# ANA_FE.net
KiCad netlist of a schematic drawn in Altium Designer
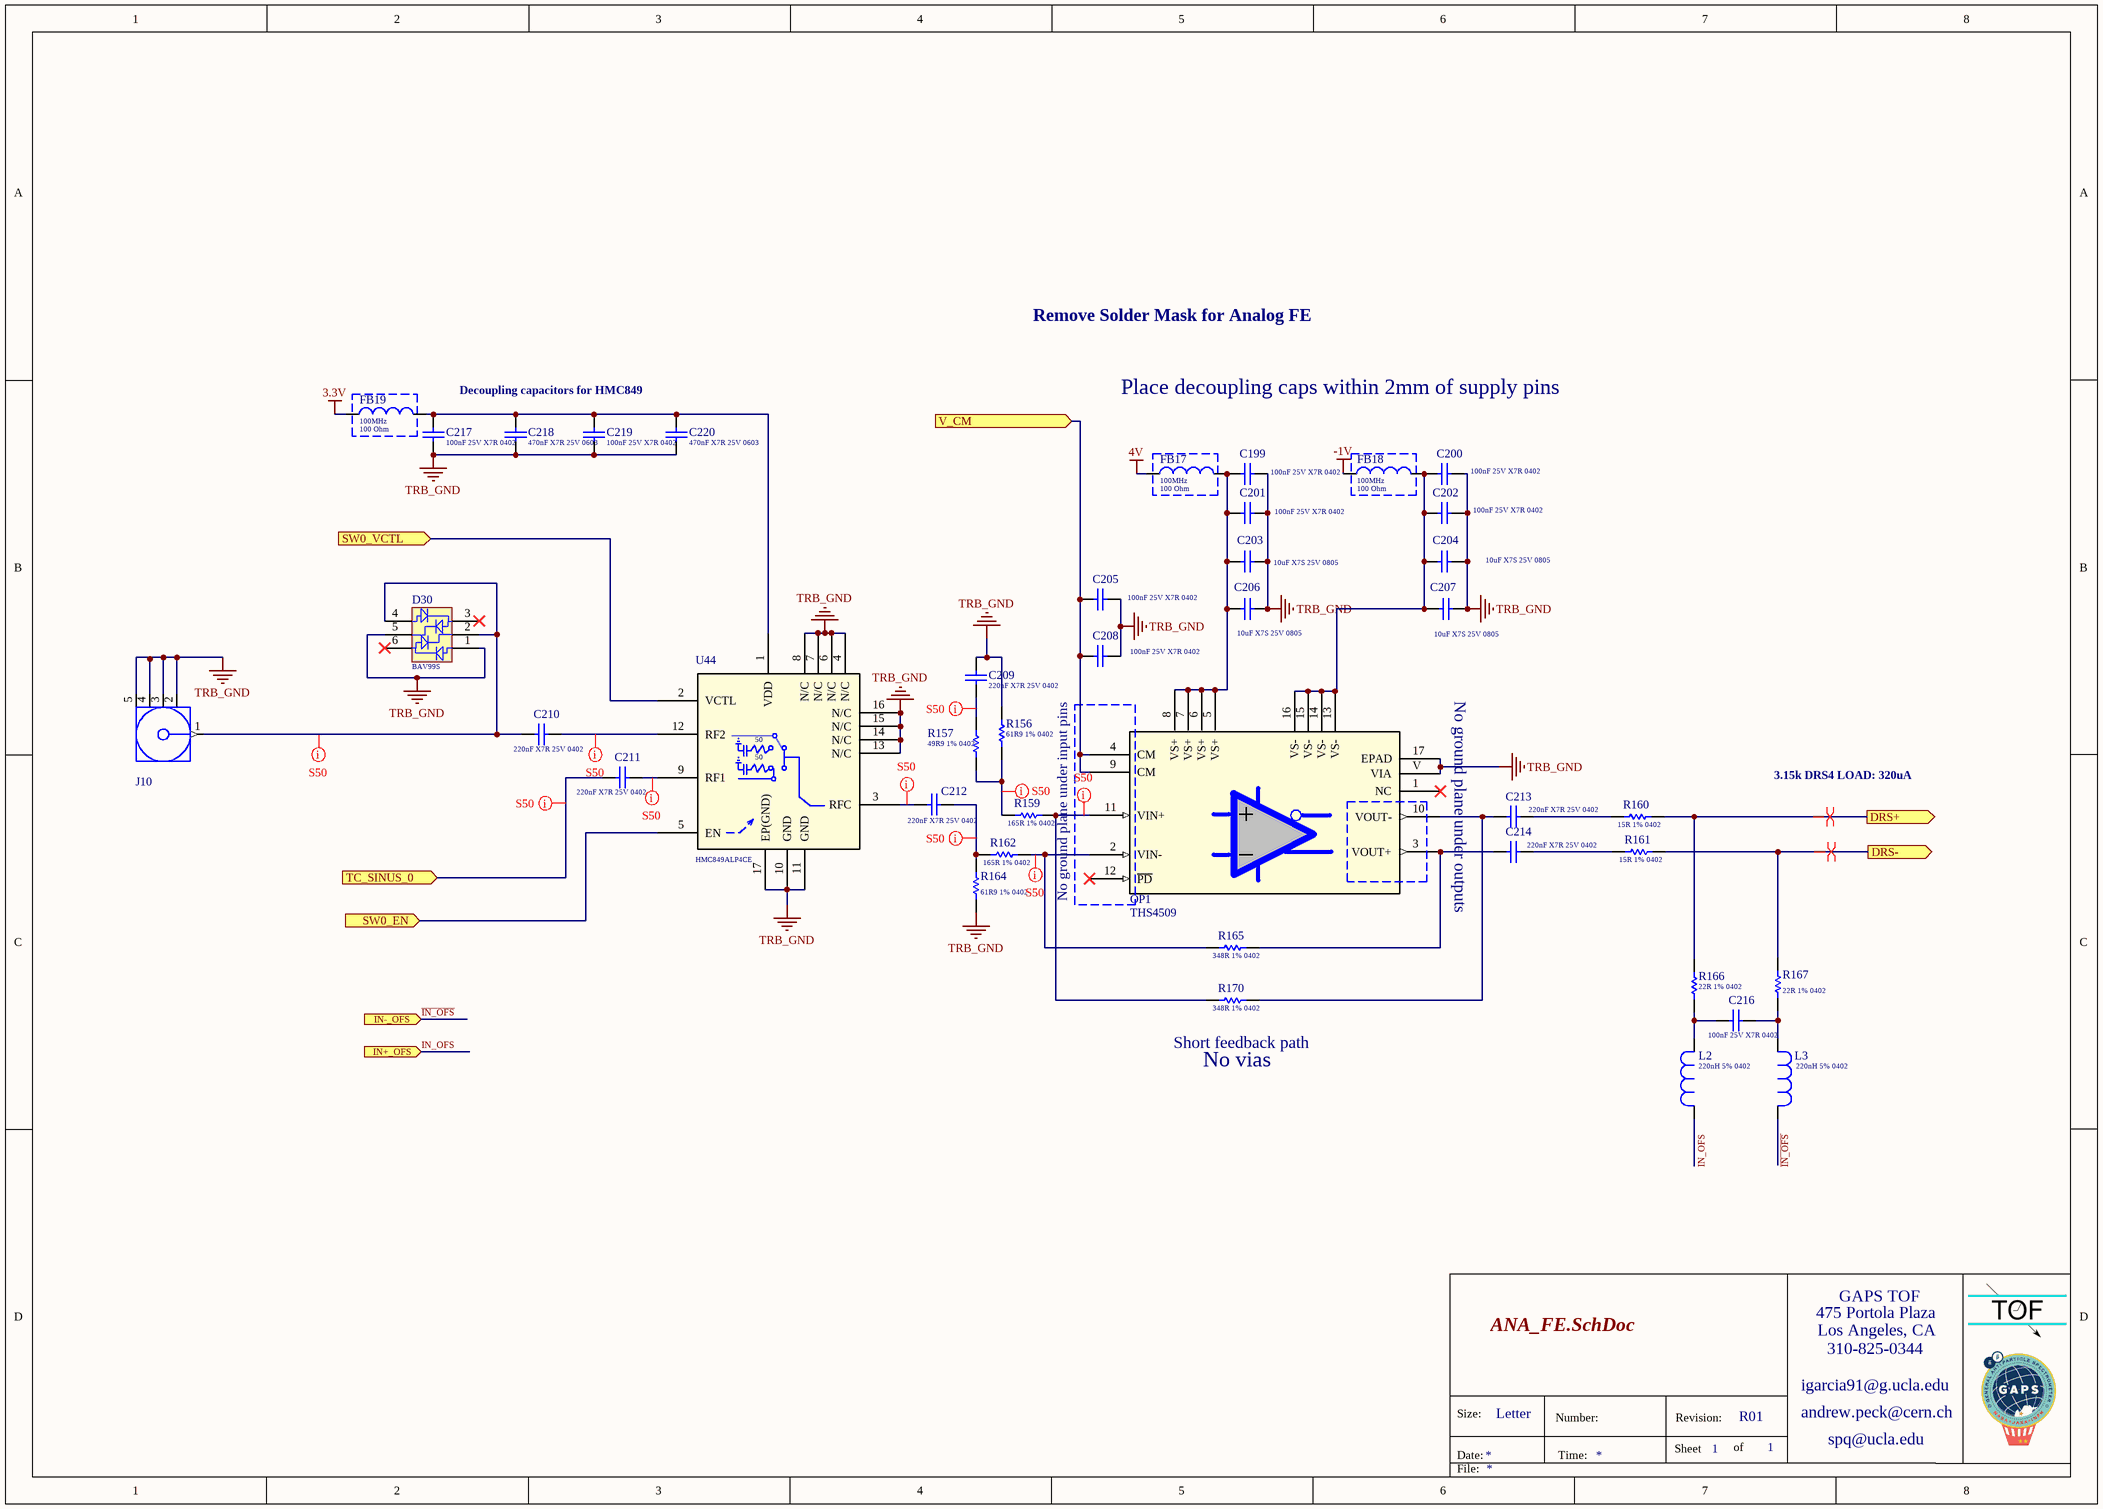
[diagram p0: ANA_FE.SchDoc]

(export (version "E")
  (design (tool "Eeschema 10.0.6"))
  (components
    (comp (ref "C199")
      (value "Cap_Taiyo_Yuden_TMK105B7104KV-FR_100nF")
      (footprint "Cap_Taiyo_Yuden_TMK105B7104KV-FR_100nF")
      (description "CAP CER 100nF 25V X7R 0402")
      (fields (field (name "CAPACITANCE") "100nF 25V X7R 0402"))
      (libsource (lib "Cap_Taiyo_Yuden_TMK105B7104KV-FR_100nF") (part "Cap_Taiyo_Yuden_TMK105B7104KV-FR_100nF"))
    )
    (comp (ref "C200")
      (value "Cap_Taiyo_Yuden_TMK105B7104KV-FR_100nF")
      (footprint "Cap_Taiyo_Yuden_TMK105B7104KV-FR_100nF")
      (description "CAP CER 100nF 25V X7R 0402")
      (fields (field (name "CAPACITANCE") "100nF 25V X7R 0402"))
      (libsource (lib "Cap_Taiyo_Yuden_TMK105B7104KV-FR_100nF") (part "Cap_Taiyo_Yuden_TMK105B7104KV-FR_100nF"))
    )
    (comp (ref "C201")
      (value "Cap_Taiyo_Yuden_TMK105B7104KV-FR_100nF")
      (footprint "Cap_Taiyo_Yuden_TMK105B7104KV-FR_100nF")
      (description "CAP CER 100nF 25V X7R 0402")
      (fields (field (name "CAPACITANCE") "100nF 25V X7R 0402"))
      (libsource (lib "Cap_Taiyo_Yuden_TMK105B7104KV-FR_100nF") (part "Cap_Taiyo_Yuden_TMK105B7104KV-FR_100nF"))
    )
    (comp (ref "C202")
      (value "Cap_Taiyo_Yuden_TMK105B7104KV-FR_100nF")
      (footprint "Cap_Taiyo_Yuden_TMK105B7104KV-FR_100nF")
      (description "CAP CER 100nF 25V X7R 0402")
      (fields (field (name "CAPACITANCE") "100nF 25V X7R 0402"))
      (libsource (lib "Cap_Taiyo_Yuden_TMK105B7104KV-FR_100nF") (part "Cap_Taiyo_Yuden_TMK105B7104KV-FR_100nF"))
    )
    (comp (ref "C203")
      (value "Cap_Murata_ GRM21BC71E106ME11L_10uF")
      (footprint "Cap_Murata_ GRM21BC71E106ME11L_10uF")
      (description "CAP CER 10uF 25V X7R 0805")
      (fields (field (name "CAPACITANCE") "10uF X7S 25V 0805"))
      (libsource (lib "Cap_Murata_ GRM21BC71E106ME11L_10uF") (part "Cap_Murata_ GRM21BC71E106ME11L_10uF"))
    )
    (comp (ref "C204")
      (value "Cap_Murata_ GRM21BC71E106ME11L_10uF")
      (footprint "Cap_Murata_ GRM21BC71E106ME11L_10uF")
      (description "CAP CER 10uF 25V X7R 0805")
      (fields (field (name "CAPACITANCE") "10uF X7S 25V 0805"))
      (libsource (lib "Cap_Murata_ GRM21BC71E106ME11L_10uF") (part "Cap_Murata_ GRM21BC71E106ME11L_10uF"))
    )
    (comp (ref "C205")
      (value "Cap_Taiyo_Yuden_TMK105B7104KV-FR_100nF")
      (footprint "Cap_Taiyo_Yuden_TMK105B7104KV-FR_100nF")
      (description "CAP CER 100nF 25V X7R 0402")
      (fields (field (name "CAPACITANCE") "100nF 25V X7R 0402"))
      (libsource (lib "Cap_Taiyo_Yuden_TMK105B7104KV-FR_100nF") (part "Cap_Taiyo_Yuden_TMK105B7104KV-FR_100nF"))
    )
    (comp (ref "C206")
      (value "Cap_Murata_ GRM21BC71E106ME11L_10uF")
      (footprint "Cap_Murata_ GRM21BC71E106ME11L_10uF")
      (description "CAP CER 10uF 25V X7R 0805")
      (fields (field (name "CAPACITANCE") "10uF X7S 25V 0805"))
      (libsource (lib "Cap_Murata_ GRM21BC71E106ME11L_10uF") (part "Cap_Murata_ GRM21BC71E106ME11L_10uF"))
    )
    (comp (ref "C207")
      (value "Cap_Murata_ GRM21BC71E106ME11L_10uF")
      (footprint "Cap_Murata_ GRM21BC71E106ME11L_10uF")
      (description "CAP CER 10uF 25V X7R 0805")
      (fields (field (name "CAPACITANCE") "10uF X7S 25V 0805"))
      (libsource (lib "Cap_Murata_ GRM21BC71E106ME11L_10uF") (part "Cap_Murata_ GRM21BC71E106ME11L_10uF"))
    )
    (comp (ref "C208")
      (value "Cap_Taiyo_Yuden_TMK105B7104KV-FR_100nF")
      (footprint "Cap_Taiyo_Yuden_TMK105B7104KV-FR_100nF")
      (description "CAP CER 100nF 25V X7R 0402")
      (fields (field (name "CAPACITANCE") "100nF 25V X7R 0402"))
      (libsource (lib "Cap_Taiyo_Yuden_TMK105B7104KV-FR_100nF") (part "Cap_Taiyo_Yuden_TMK105B7104KV-FR_100nF"))
    )
    (comp (ref "C209")
      (value "Cap_TDK_C1608X5R1A106M080AC_220nF")
      (footprint "Cap_TDK_C1608X5R1A106M080AC_220nF")
      (description "CAP CER 220nF 50V X7R 0402")
      (fields (field (name "CAPACITANCE") "220nF X7R 25V 0402"))
      (libsource (lib "Cap_TDK_C1608X5R1A106M080AC_220nF") (part "Cap_TDK_C1608X5R1A106M080AC_220nF"))
    )
    (comp (ref "C210")
      (value "Cap_TDK_C1608X5R1A106M080AC_220nF")
      (footprint "Cap_TDK_C1608X5R1A106M080AC_220nF")
      (description "CAP CER 220nF 50V X7R 0402")
      (fields (field (name "CAPACITANCE") "220nF X7R 25V 0402"))
      (libsource (lib "Cap_TDK_C1608X5R1A106M080AC_220nF") (part "Cap_TDK_C1608X5R1A106M080AC_220nF"))
    )
    (comp (ref "C211")
      (value "Cap_TDK_C1608X5R1A106M080AC_220nF")
      (footprint "Cap_TDK_C1608X5R1A106M080AC_220nF")
      (description "CAP CER 220nF 50V X7R 0402")
      (fields (field (name "CAPACITANCE") "220nF X7R 25V 0402"))
      (libsource (lib "Cap_TDK_C1608X5R1A106M080AC_220nF") (part "Cap_TDK_C1608X5R1A106M080AC_220nF"))
    )
    (comp (ref "C212")
      (value "Cap_TDK_C1608X5R1A106M080AC_220nF")
      (footprint "Cap_TDK_C1608X5R1A106M080AC_220nF")
      (description "CAP CER 220nF 50V X7R 0402")
      (fields (field (name "CAPACITANCE") "220nF X7R 25V 0402"))
      (libsource (lib "Cap_TDK_C1608X5R1A106M080AC_220nF") (part "Cap_TDK_C1608X5R1A106M080AC_220nF"))
    )
    (comp (ref "C213")
      (value "Cap_TDK_C1608X5R1A106M080AC_220nF")
      (footprint "Cap_TDK_C1608X5R1A106M080AC_220nF")
      (description "CAP CER 220nF 50V X7R 0402")
      (fields (field (name "CAPACITANCE") "220nF X7R 25V 0402"))
      (libsource (lib "Cap_TDK_C1608X5R1A106M080AC_220nF") (part "Cap_TDK_C1608X5R1A106M080AC_220nF"))
    )
    (comp (ref "C214")
      (value "Cap_TDK_C1608X5R1A106M080AC_220nF")
      (footprint "Cap_TDK_C1608X5R1A106M080AC_220nF")
      (description "CAP CER 220nF 50V X7R 0402")
      (fields (field (name "CAPACITANCE") "220nF X7R 25V 0402"))
      (libsource (lib "Cap_TDK_C1608X5R1A106M080AC_220nF") (part "Cap_TDK_C1608X5R1A106M080AC_220nF"))
    )
    (comp (ref "C216")
      (value "Cap_Taiyo_Yuden_TMK105B7104KV-FR_100nF")
      (footprint "Cap_Taiyo_Yuden_TMK105B7104KV-FR_100nF")
      (description "CAP CER 100nF 25V X7R 0402")
      (fields (field (name "CAPACITANCE") "100nF 25V X7R 0402"))
      (libsource (lib "Cap_Taiyo_Yuden_TMK105B7104KV-FR_100nF") (part "Cap_Taiyo_Yuden_TMK105B7104KV-FR_100nF"))
    )
    (comp (ref "C217")
      (value "Cap_Taiyo_Yuden_TMK105B7104KV-FR_100nF")
      (footprint "Cap_Taiyo_Yuden_TMK105B7104KV-FR_100nF")
      (description "CAP CER 100nF 25V X7R 0402")
      (fields (field (name "CAPACITANCE") "100nF 25V X7R 0402"))
      (libsource (lib "Cap_Taiyo_Yuden_TMK105B7104KV-FR_100nF") (part "Cap_Taiyo_Yuden_TMK105B7104KV-FR_100nF"))
    )
    (comp (ref "C218")
      (value "Cap_Wurth_Electronics_885012206075_470nF")
      (footprint "Cap_Wurth_Electronics_885012206075_470nF")
      (description "CAP CER 470nF 25V X7R 0603")
      (fields (field (name "CAPACITANCE") "470nF X7R 25V 0603"))
      (libsource (lib "Cap_Wurth_Electronics_885012206075_470nF") (part "Cap_Wurth_Electronics_885012206075_470nF"))
    )
    (comp (ref "C219")
      (value "Cap_Taiyo_Yuden_TMK105B7104KV-FR_100nF")
      (footprint "Cap_Taiyo_Yuden_TMK105B7104KV-FR_100nF")
      (description "CAP CER 100nF 25V X7R 0402")
      (fields (field (name "CAPACITANCE") "100nF 25V X7R 0402"))
      (libsource (lib "Cap_Taiyo_Yuden_TMK105B7104KV-FR_100nF") (part "Cap_Taiyo_Yuden_TMK105B7104KV-FR_100nF"))
    )
    (comp (ref "C220")
      (value "Cap_Wurth_Electronics_885012206075_470nF")
      (footprint "Cap_Wurth_Electronics_885012206075_470nF")
      (description "CAP CER 470nF 25V X7R 0603")
      (fields (field (name "CAPACITANCE") "470nF X7R 25V 0603"))
      (libsource (lib "Cap_Wurth_Electronics_885012206075_470nF") (part "Cap_Wurth_Electronics_885012206075_470nF"))
    )
    (comp (ref "D30")
      (value "BAV99S")
      (footprint "INF-SOT363_V")
      (description "Silicon Switching Diode, SOT363, Reel, Green")
      (fields (field (name "MANUFACTURER") "Infineon"))
      (libsource (lib "Altium Content Vault") (part "INF-D_A1K2C3A4K5C6-6"))
    )
    (comp (ref "FB17")
      (value "742792731")
      (footprint "FB_Wurth_Electronics_742792731_100Ohms")
      (description "FB SMD 100 OHM 25% 1.2A 0402")
      (fields (field (name "MEASURING FREQUENCY") "100MHz") (field (name "IMPEDANCE") "100 Ohm"))
      (libsource (lib "FB_Wurth_Electronics_742792731_100Ohms") (part "FB_Wurth_Electronics_742792731_100Ohms"))
    )
    (comp (ref "FB18")
      (value "742792731")
      (footprint "FB_Wurth_Electronics_742792731_100Ohms")
      (description "FB SMD 100 OHM 25% 1.2A 0402")
      (fields (field (name "MEASURING FREQUENCY") "100MHz") (field (name "IMPEDANCE") "100 Ohm"))
      (libsource (lib "FB_Wurth_Electronics_742792731_100Ohms") (part "FB_Wurth_Electronics_742792731_100Ohms"))
    )
    (comp (ref "FB19")
      (value "742792731")
      (footprint "FB_Wurth_Electronics_742792731_100Ohms")
      (description "FB SMD 100 OHM 25% 1.2A 0402")
      (fields (field (name "MEASURING FREQUENCY") "100MHz") (field (name "IMPEDANCE") "100 Ohm"))
      (libsource (lib "FB_Wurth_Electronics_742792731_100Ohms") (part "FB_Wurth_Electronics_742792731_100Ohms"))
    )
    (comp (ref "J10")
      (value "CONREVSMA003.062")
      (footprint "CON-SMA-EDGE062")
      (libsource (lib "Altium Content Vault") (part "CN-1P-F-RF5"))
    )
    (comp (ref "L2")
      (value "Ind_TDK_ MLG1005SR22JT000_220nH")
      (footprint "Ind_TDK_ MLG1005SR22JT000_220nH")
      (description "Fixed Inductors .22 UH 5%")
      (fields (field (name "INDUCTANCE") "220nH 5% 0402"))
      (libsource (lib "Ind_TDK_ MLG1005SR22JT000_220nH") (part "Ind_TDK_ MLG1005SR22JT000_220nH"))
    )
    (comp (ref "L3")
      (value "Ind_TDK_ MLG1005SR22JT000_220nH")
      (footprint "Ind_TDK_ MLG1005SR22JT000_220nH")
      (description "Fixed Inductors .22 UH 5%")
      (fields (field (name "INDUCTANCE") "220nH 5% 0402"))
      (libsource (lib "Ind_TDK_ MLG1005SR22JT000_220nH") (part "Ind_TDK_ MLG1005SR22JT000_220nH"))
    )
    (comp (ref "OP1")
      (value "THS4509")
      (footprint "RGT16")
      (description "Imported")
      (fields (field (name "MANUFACTURER_PART_NUMBER") "THS4509RGTT"))
      (libsource (lib "THS4509RGTT") (part "THS4509RGTT"))
    )
    (comp (ref "R156")
      (value "61R9 1% 0402")
      (footprint "RESC0402(1005)_L")
      (description "61R9 0.063W 1% 0402 (1005 Metric)  SMD")
      (fields (field (name "TOLERANCE") "1 %") (field (name "POWER") "0.063 W"))
      (libsource (lib "Altium Content Vault") (part "RES"))
    )
    (comp (ref "R157")
      (value "49R9 1% 0402")
      (footprint "RESC0402(1005)_L")
      (description "49R9 0.063W 1% 0402 (1005 Metric)  SMD")
      (fields (field (name "POWER") "0.063 W") (field (name "TOLERANCE") "1 %"))
      (libsource (lib "Altium Content Vault") (part "RES"))
    )
    (comp (ref "R159")
      (value "165R 1% 0402")
      (footprint "RESC0402(1005)_L")
      (description "165R 0.063W 1% 0402 (1005 Metric)  SMD")
      (fields (field (name "POWER") "0.063 W") (field (name "TOLERANCE") "1 %"))
      (libsource (lib "Altium Content Vault") (part "RES"))
    )
    (comp (ref "R160")
      (value "15R 1% 0402")
      (footprint "RESC0402(1005)_L")
      (description "15R 0.063W 1% 0402 (1005 Metric)  SMD")
      (fields (field (name "TOLERANCE") "1 %") (field (name "POWER") "0.063 W"))
      (libsource (lib "Altium Content Vault") (part "RES"))
    )
    (comp (ref "R161")
      (value "15R 1% 0402")
      (footprint "RESC0402(1005)_L")
      (description "15R 0.063W 1% 0402 (1005 Metric)  SMD")
      (fields (field (name "TOLERANCE") "1 %") (field (name "POWER") "0.063 W"))
      (libsource (lib "Altium Content Vault") (part "RES"))
    )
    (comp (ref "R162")
      (value "165R 1% 0402")
      (footprint "RESC0402(1005)_L")
      (description "165R 0.063W 1% 0402 (1005 Metric)  SMD")
      (fields (field (name "POWER") "0.063 W") (field (name "TOLERANCE") "1 %"))
      (libsource (lib "Altium Content Vault") (part "RES"))
    )
    (comp (ref "R164")
      (value "61R9 1% 0402")
      (footprint "RESC0402(1005)_L")
      (description "61R9 0.063W 1% 0402 (1005 Metric)  SMD")
      (fields (field (name "TOLERANCE") "1 %") (field (name "POWER") "0.063 W"))
      (libsource (lib "Altium Content Vault") (part "RES"))
    )
    (comp (ref "R165")
      (value "348R 1% 0402")
      (footprint "RESC0402(1005)_L")
      (description "348R 0.063W 1% 0402 (1005 Metric)  SMD")
      (fields (field (name "TOLERANCE") "1 %") (field (name "POWER") "0.063 W"))
      (libsource (lib "Altium Content Vault") (part "RES"))
    )
    (comp (ref "R166")
      (value "22R 1% 0402")
      (footprint "RESC0402(1005)_L")
      (description "22R 0.063W 1% 0402 (1005 Metric)  SMD")
      (fields (field (name "TOLERANCE") "1 %") (field (name "POWER") "0.063 W"))
      (libsource (lib "Altium Content Vault") (part "RES"))
    )
    (comp (ref "R167")
      (value "22R 1% 0402")
      (footprint "RESC0402(1005)_L")
      (description "22R 0.063W 1% 0402 (1005 Metric)  SMD")
      (fields (field (name "TOLERANCE") "1 %") (field (name "POWER") "0.063 W"))
      (libsource (lib "Altium Content Vault") (part "RES"))
    )
    (comp (ref "R170")
      (value "348R 1% 0402")
      (footprint "RESC0402(1005)_L")
      (description "348R 0.063W 1% 0402 (1005 Metric)  SMD")
      (fields (field (name "TOLERANCE") "1 %") (field (name "POWER") "0.063 W"))
      (libsource (lib "Altium Content Vault") (part "RES"))
    )
    (comp (ref "U44")
      (value "HMC849")
      (footprint "CP_16_40")
      (description "RF Switch ICs DC-6 GHZ Hi Isolation Switch")
      (fields (field (name "MANUFACTURER_PART_NUMBER") "HMC849ALP4CE") (field (name "SERIES") "HMC849ALP4CE"))
      (libsource (lib "HMC849ALP4CE") (part "HMC849ALP4CE"))
    )
  )
  (nets
    (net (code "1") (name "-1V") (class "Default")
      (node (ref "FB18") (pin "1") (pinfunction "1_1") (pintype "passive"))
    )
    (net (code "2") (name "/DRS+") (class "Default")
      (node (ref "R160") (pin "2") (pinfunction "2_2") (pintype "passive"))
      (node (ref "R166") (pin "2") (pinfunction "2_2") (pintype "passive"))
    )
    (net (code "3") (name "/DRS-") (class "Default")
      (node (ref "R161") (pin "2") (pinfunction "2_2") (pintype "passive"))
      (node (ref "R167") (pin "2") (pinfunction "2_2") (pintype "passive"))
    )
    (net (code "4") (name "/IN_OFS") (class "Default")
      (node (ref "L2") (pin "2") (pinfunction "2_2") (pintype "passive"))
    )
    (net (code "5") (name "/SW0_EN") (class "Default")
      (node (ref "U44") (pin "5") (pinfunction "EN_5") (pintype "passive"))
    )
    (net (code "6") (name "/SW0_VCTL") (class "Default")
      (node (ref "U44") (pin "2") (pinfunction "VCTL_2") (pintype "passive"))
    )
    (net (code "7") (name "/TC_SINUS_0") (class "Default")
      (node (ref "C211") (pin "2") (pinfunction "2_2") (pintype "passive"))
    )
    (net (code "8") (name "/V_CM") (class "Default")
      (node (ref "C205") (pin "1") (pinfunction "1_1") (pintype "passive"))
      (node (ref "C208") (pin "1") (pinfunction "1_1") (pintype "passive"))
      (node (ref "OP1") (pin "4") (pinfunction "CM_4") (pintype "passive"))
      (node (ref "OP1") (pin "9") (pinfunction "CM_9") (pintype "passive"))
    )
    (net (code "9") (name "/~{IN_OFS}") (class "Default")
      (node (ref "L3") (pin "1") (pinfunction "1_1") (pintype "passive"))
    )
    (net (code "10") (name "3.3V") (class "Default")
      (node (ref "FB19") (pin "1") (pinfunction "1_1") (pintype "passive"))
    )
    (net (code "11") (name "4V") (class "Default")
      (node (ref "FB17") (pin "1") (pinfunction "1_1") (pintype "passive"))
    )
    (net (code "12") (name "Net-(C199-Pad1)") (class "Default")
      (node (ref "C199") (pin "1") (pinfunction "1_1") (pintype "passive"))
      (node (ref "C201") (pin "1") (pinfunction "1_1") (pintype "passive"))
      (node (ref "C203") (pin "2") (pinfunction "2_2") (pintype "passive"))
      (node (ref "C206") (pin "2") (pinfunction "2_2") (pintype "passive"))
      (node (ref "FB17") (pin "2") (pinfunction "2_2") (pintype "passive"))
      (node (ref "OP1") (pin "5") (pinfunction "VS+_5") (pintype "power_in"))
      (node (ref "OP1") (pin "6") (pinfunction "VS+_6") (pintype "power_in"))
      (node (ref "OP1") (pin "7") (pinfunction "VS+_7") (pintype "power_in"))
      (node (ref "OP1") (pin "8") (pinfunction "VS+_8") (pintype "power_in"))
    )
    (net (code "13") (name "Net-(C200-Pad1)") (class "Default")
      (node (ref "C200") (pin "1") (pinfunction "1_1") (pintype "passive"))
      (node (ref "C202") (pin "1") (pinfunction "1_1") (pintype "passive"))
      (node (ref "C204") (pin "2") (pinfunction "2_2") (pintype "passive"))
      (node (ref "C207") (pin "2") (pinfunction "2_2") (pintype "passive"))
      (node (ref "FB18") (pin "2") (pinfunction "2_2") (pintype "passive"))
      (node (ref "OP1") (pin "13") (pinfunction "VS-_13") (pintype "power_in"))
      (node (ref "OP1") (pin "14") (pinfunction "VS-_14") (pintype "power_in"))
      (node (ref "OP1") (pin "15") (pinfunction "VS-_15") (pintype "power_in"))
      (node (ref "OP1") (pin "16") (pinfunction "VS-_16") (pintype "power_in"))
    )
    (net (code "14") (name "Net-(C209-Pad2)") (class "Default")
      (node (ref "C209") (pin "2") (pinfunction "2_2") (pintype "passive"))
      (node (ref "R157") (pin "2") (pinfunction "2_2") (pintype "passive"))
    )
    (net (code "15") (name "Net-(C212-Pad1)") (class "Default")
      (node (ref "C212") (pin "1") (pinfunction "1_1") (pintype "passive"))
      (node (ref "R162") (pin "1") (pinfunction "1_1") (pintype "passive"))
      (node (ref "R164") (pin "2") (pinfunction "2_2") (pintype "passive"))
    )
    (net (code "16") (name "Net-(C213-Pad1)") (class "Default")
      (node (ref "C213") (pin "1") (pinfunction "1_1") (pintype "passive"))
      (node (ref "R160") (pin "1") (pinfunction "1_1") (pintype "passive"))
    )
    (net (code "17") (name "Net-(C214-Pad1)") (class "Default")
      (node (ref "C214") (pin "1") (pinfunction "1_1") (pintype "passive"))
      (node (ref "R161") (pin "1") (pinfunction "1_1") (pintype "passive"))
    )
    (net (code "18") (name "Net-(C216-Pad1)") (class "Default")
      (node (ref "C216") (pin "1") (pinfunction "1_1") (pintype "passive"))
      (node (ref "L2") (pin "1") (pinfunction "1_1") (pintype "passive"))
      (node (ref "R166") (pin "1") (pinfunction "1_1") (pintype "passive"))
    )
    (net (code "19") (name "Net-(C216-Pad2)") (class "Default")
      (node (ref "C216") (pin "2") (pinfunction "2_2") (pintype "passive"))
      (node (ref "L3") (pin "2") (pinfunction "2_2") (pintype "passive"))
      (node (ref "R167") (pin "1") (pinfunction "1_1") (pintype "passive"))
    )
    (net (code "20") (name "Net-(D30-A4)") (class "Default")
      (node (ref "C210") (pin "2") (pinfunction "2_2") (pintype "passive"))
      (node (ref "D30") (pin "2") (pinfunction "K2_2") (pintype "passive"))
      (node (ref "D30") (pin "4") (pinfunction "A4_4") (pintype "passive"))
      (node (ref "J10") (pin "1") (pinfunction "Signal_1") (pintype "output"))
    )
    (net (code "21") (name "Net-(OP1-VIN+)") (class "Default")
      (node (ref "OP1") (pin "11") (pinfunction "VIN+_11") (pintype "input"))
      (node (ref "R159") (pin "2") (pinfunction "2_2") (pintype "passive"))
      (node (ref "R170") (pin "1") (pinfunction "1_1") (pintype "passive"))
    )
    (net (code "22") (name "Net-(OP1-VIN-)") (class "Default")
      (node (ref "OP1") (pin "2") (pinfunction "VIN-_2") (pintype "input"))
      (node (ref "R162") (pin "2") (pinfunction "2_2") (pintype "passive"))
      (node (ref "R165") (pin "1") (pinfunction "1_1") (pintype "passive"))
    )
    (net (code "23") (name "Net-(OP1-VOUT+)") (class "Default")
      (node (ref "C214") (pin "2") (pinfunction "2_2") (pintype "passive"))
      (node (ref "OP1") (pin "3") (pinfunction "VOUT+_3") (pintype "output"))
      (node (ref "R165") (pin "2") (pinfunction "2_2") (pintype "passive"))
    )
    (net (code "24") (name "Net-(OP1-VOUT-)") (class "Default")
      (node (ref "C213") (pin "2") (pinfunction "2_2") (pintype "passive"))
      (node (ref "OP1") (pin "10") (pinfunction "VOUT-_10") (pintype "output"))
      (node (ref "R170") (pin "2") (pinfunction "2_2") (pintype "passive"))
    )
    (net (code "25") (name "Net-(R156-Pad1)") (class "Default")
      (node (ref "R156") (pin "1") (pinfunction "1_1") (pintype "passive"))
      (node (ref "R157") (pin "1") (pinfunction "1_1") (pintype "passive"))
      (node (ref "R159") (pin "1") (pinfunction "1_1") (pintype "passive"))
    )
    (net (code "26") (name "Net-(U44-RF1)") (class "Default")
      (node (ref "C211") (pin "1") (pinfunction "1_1") (pintype "passive"))
      (node (ref "U44") (pin "9") (pinfunction "RF1_9") (pintype "passive"))
    )
    (net (code "27") (name "Net-(U44-RF2)") (class "Default")
      (node (ref "C210") (pin "1") (pinfunction "1_1") (pintype "passive"))
      (node (ref "U44") (pin "12") (pinfunction "RF2_12") (pintype "passive"))
    )
    (net (code "28") (name "Net-(U44-RFC)") (class "Default")
      (node (ref "C212") (pin "2") (pinfunction "2_2") (pintype "passive"))
      (node (ref "U44") (pin "3") (pinfunction "RFC_3") (pintype "passive"))
    )
    (net (code "29") (name "Net-(U44-VDD)") (class "Default")
      (node (ref "C217") (pin "2") (pinfunction "2_2") (pintype "passive"))
      (node (ref "C218") (pin "1") (pinfunction "1_1") (pintype "passive"))
      (node (ref "C219") (pin "2") (pinfunction "2_2") (pintype "passive"))
      (node (ref "C220") (pin "1") (pinfunction "1_1") (pintype "passive"))
      (node (ref "FB19") (pin "2") (pinfunction "2_2") (pintype "passive"))
      (node (ref "U44") (pin "1") (pinfunction "VDD_1") (pintype "passive"))
    )
    (net (code "30") (name "TRB_GND") (class "Default")
      (node (ref "C199") (pin "2") (pinfunction "2_2") (pintype "passive"))
      (node (ref "C200") (pin "2") (pinfunction "2_2") (pintype "passive"))
      (node (ref "C201") (pin "2") (pinfunction "2_2") (pintype "passive"))
      (node (ref "C202") (pin "2") (pinfunction "2_2") (pintype "passive"))
      (node (ref "C203") (pin "1") (pinfunction "1_1") (pintype "passive"))
      (node (ref "C204") (pin "1") (pinfunction "1_1") (pintype "passive"))
      (node (ref "C205") (pin "2") (pinfunction "2_2") (pintype "passive"))
      (node (ref "C206") (pin "1") (pinfunction "1_1") (pintype "passive"))
      (node (ref "C207") (pin "1") (pinfunction "1_1") (pintype "passive"))
      (node (ref "C208") (pin "2") (pinfunction "2_2") (pintype "passive"))
      (node (ref "C209") (pin "1") (pinfunction "1_1") (pintype "passive"))
      (node (ref "C217") (pin "1") (pinfunction "1_1") (pintype "passive"))
      (node (ref "C218") (pin "2") (pinfunction "2_2") (pintype "passive"))
      (node (ref "C219") (pin "1") (pinfunction "1_1") (pintype "passive"))
      (node (ref "C220") (pin "2") (pinfunction "2_2") (pintype "passive"))
      (node (ref "D30") (pin "1") (pinfunction "A1_1") (pintype "passive"))
      (node (ref "D30") (pin "5") (pinfunction "K5_5") (pintype "passive"))
      (node (ref "J10") (pin "2") (pinfunction "GND_2") (pintype "power_in"))
      (node (ref "J10") (pin "3") (pinfunction "GND_3") (pintype "power_in"))
      (node (ref "J10") (pin "4") (pinfunction "GND_4") (pintype "power_in"))
      (node (ref "J10") (pin "5") (pinfunction "GND_5") (pintype "power_in"))
      (node (ref "OP1") (pin "17") (pinfunction "EPAD_17") (pintype "passive"))
      (node (ref "OP1") (pin "V") (pinfunction "VIA_V") (pintype "passive"))
      (node (ref "R156") (pin "2") (pinfunction "2_2") (pintype "passive"))
      (node (ref "R164") (pin "1") (pinfunction "1_1") (pintype "passive"))
      (node (ref "U44") (pin "10") (pinfunction "GND_10") (pintype "passive"))
      (node (ref "U44") (pin "11") (pinfunction "GND_11") (pintype "passive"))
      (node (ref "U44") (pin "13") (pinfunction "N/C_13") (pintype "passive"))
      (node (ref "U44") (pin "14") (pinfunction "N/C_14") (pintype "passive"))
      (node (ref "U44") (pin "15") (pinfunction "N/C_15") (pintype "passive"))
      (node (ref "U44") (pin "16") (pinfunction "N/C_16") (pintype "passive"))
      (node (ref "U44") (pin "17") (pinfunction "EP(GND)_17") (pintype "passive"))
      (node (ref "U44") (pin "4") (pinfunction "N/C_4") (pintype "passive"))
      (node (ref "U44") (pin "6") (pinfunction "N/C_6") (pintype "passive"))
      (node (ref "U44") (pin "7") (pinfunction "N/C_7") (pintype "passive"))
      (node (ref "U44") (pin "8") (pinfunction "N/C_8") (pintype "passive"))
    )
    (net (code "31") (name "unconnected-(D30-C3-Pad3)") (class "Default")
      (node (ref "D30") (pin "3") (pinfunction "C3_3") (pintype "passive+no_connect"))
    )
    (net (code "32") (name "unconnected-(D30-C6-Pad6)") (class "Default")
      (node (ref "D30") (pin "6") (pinfunction "C6_6") (pintype "passive+no_connect"))
    )
    (net (code "33") (name "unconnected-(OP1-NC-Pad1)") (class "Default")
      (node (ref "OP1") (pin "1") (pinfunction "NC_1") (pintype "passive+no_connect"))
    )
    (net (code "34") (name "unconnected-(OP1-~{PD}-Pad12)") (class "Default")
      (node (ref "OP1") (pin "12") (pinfunction "~{PD}_12") (pintype "input+no_connect"))
    )
  )
)
